# Nguyen_Ly.net
KiCad netlist of a schematic drawn in Altium Designer
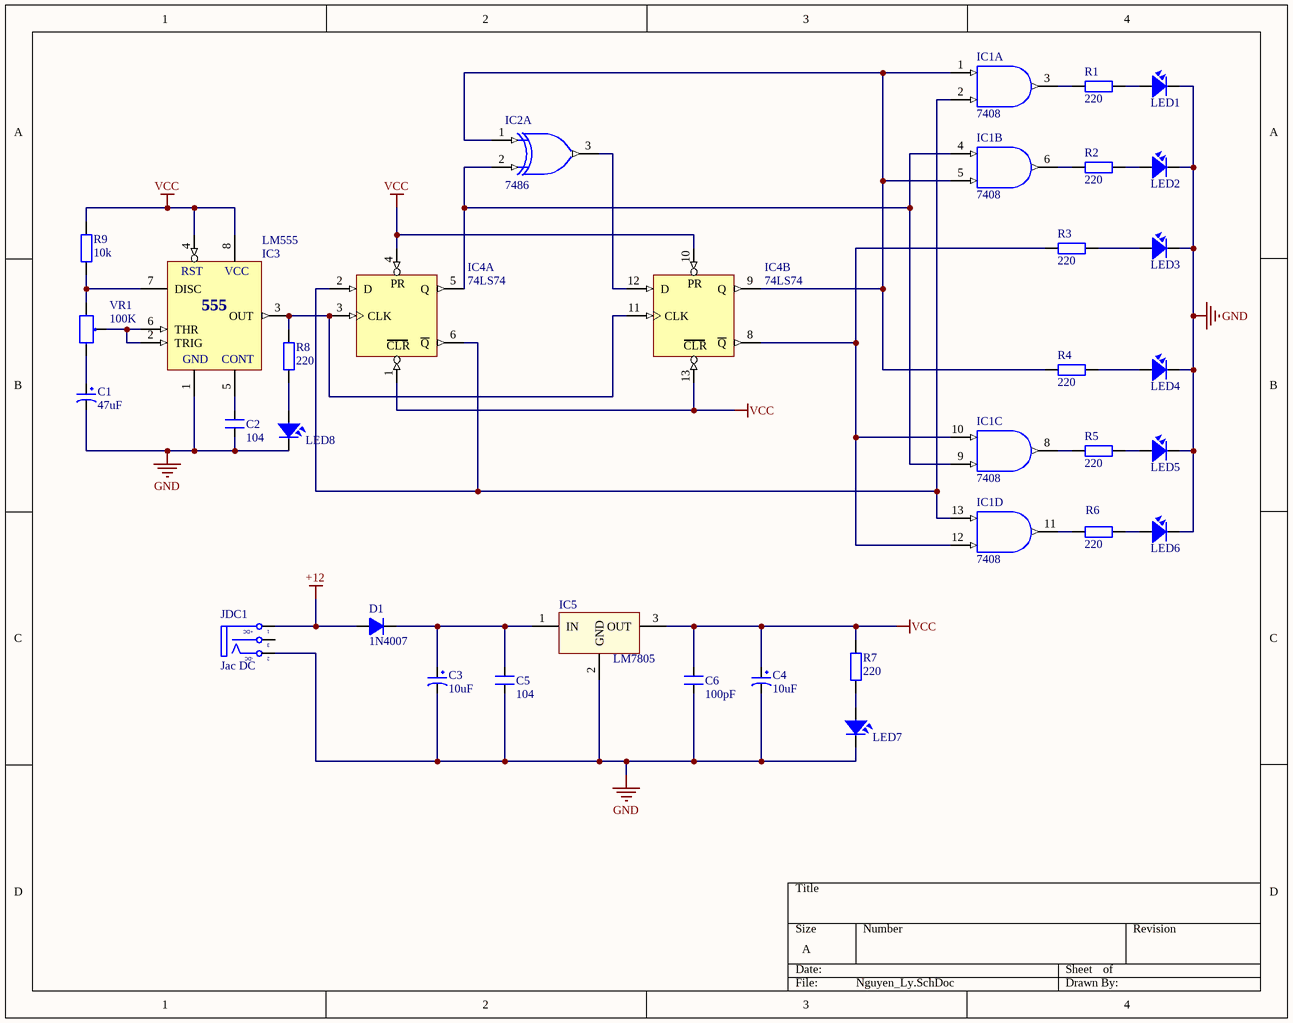
[diagram p0: Nguyen_Ly.SchDoc]

(export (version "E")
  (design (tool "Eeschema 10.0.6"))
  (components
    (comp (ref "C1")
      (value "47uF")
      (footprint "CP1/2")
      (description "Cap P  0,1uF < 22uF , 16 - 50V")
      (libsource (lib "Thuvien3D") (part "CP1"))
    )
    (comp (ref "C2")
      (value "104")
      (footprint "CN1")
      (description "Cap np  1pF - 472pF")
      (libsource (lib "Thuvien3D") (part "CN1"))
    )
    (comp (ref "C3")
      (value "10uF")
      (footprint "CP1/2")
      (description "Cap P  0,1uF < 22uF , 16 - 50V")
      (libsource (lib "Thuvien3D") (part "CP1"))
    )
    (comp (ref "C4")
      (value "10uF")
      (footprint "CP1/2")
      (description "Cap P  0,1uF < 22uF , 16 - 50V")
      (libsource (lib "Thuvien3D") (part "CP1"))
    )
    (comp (ref "C5")
      (value "104")
      (footprint "CN1")
      (description "Cap np  1pF - 472pF")
      (libsource (lib "Thuvien3D") (part "CN1"))
    )
    (comp (ref "C6")
      (value "100pF")
      (footprint "CN1")
      (description "Cap np  1pF - 472pF")
      (libsource (lib "Thuvien3D") (part "CN1"))
    )
    (comp (ref "D1")
      (value "1N4007")
      (footprint "D1A")
      (description "Diode 1A")
      (libsource (lib "Thuvien3D") (part "D1A"))
    )
    (comp (ref "IC1")
      (value "7408")
      (footprint "DIP14/W0.3")
      (description "Quad 2-Input AND Gate")
      (libsource (lib "Thuvien3D") (part "7408"))
    )
    (comp (ref "IC2")
      (value "7486")
      (footprint "DIP14/W0.3")
      (description "Quad 2-Input XOR Gate")
      (fields (field (name "COPYRIGHT BY") "VanDungEvn@Gmail.com"))
      (libsource (lib "Thuvien3D") (part "7486"))
    )
    (comp (ref "IC3")
      (value "LM555")
      (footprint "DIP8/W0.3")
      (description "Timer")
      (libsource (lib "Thuvien3D") (part "LM555"))
    )
    (comp (ref "IC4")
      (value "74LS74")
      (footprint "DIP14/W0.3")
      (description "Dual D Flip-Flop")
      (fields (field (name "COPYRIGHT BY") "VanDungEvn@Gmail.com"))
      (libsource (lib "Thuvien3D") (part "7474"))
    )
    (comp (ref "IC5")
      (value "LM7805")
      (footprint "QTO-220")
      (description "On ap +, from + 5 to + 24VDC")
      (libsource (lib "Thuvien3D") (part "LM78xx"))
    )
    (comp (ref "JDC1")
      (value "Jac DC")
      (footprint "DC-IN")
      (description "Jac DC input")
      (libsource (lib "Thuvien3D") (part "DCIN"))
    )
    (comp (ref "LED1")
      (value "LED")
      (footprint "LED-5-Green")
      (description "LED Single colour Green and Red")
      (libsource (lib "Thuvien3D") (part "LED"))
    )
    (comp (ref "LED2")
      (value "LED")
      (footprint "LED-5-Yellow")
      (description "LED Single colour Green and Red")
      (libsource (lib "Thuvien3D") (part "LED"))
    )
    (comp (ref "LED3")
      (value "LED")
      (footprint "LED-5-RED")
      (description "LED Single colour Green and Red")
      (libsource (lib "Thuvien3D") (part "LED"))
    )
    (comp (ref "LED4")
      (value "LED")
      (footprint "LED-5-RED")
      (description "LED Single colour Green and Red")
      (libsource (lib "Thuvien3D") (part "LED"))
    )
    (comp (ref "LED5")
      (value "LED")
      (footprint "LED-5-Yellow")
      (description "LED Single colour Green and Red")
      (libsource (lib "Thuvien3D") (part "LED"))
    )
    (comp (ref "LED6")
      (value "LED")
      (footprint "LED-5-Green")
      (description "LED Single colour Green and Red")
      (libsource (lib "Thuvien3D") (part "LED"))
    )
    (comp (ref "LED7")
      (value "LED")
      (footprint "LED-5-WHITE")
      (description "LED Single colour Green and Red")
      (libsource (lib "Thuvien3D") (part "LED"))
    )
    (comp (ref "LED8")
      (value "LED")
      (footprint "LED-5-WHITE")
      (description "LED Single colour Green and Red")
      (libsource (lib "Thuvien3D") (part "LED"))
    )
    (comp (ref "R1")
      (value "220")
      (footprint "R1/4W")
      (description "Resistor 1/4W")
      (libsource (lib "Thuvien3D") (part "R1/4W"))
    )
    (comp (ref "R2")
      (value "220")
      (footprint "R1/4W")
      (description "Resistor 1/4W")
      (libsource (lib "Thuvien3D") (part "R1/4W"))
    )
    (comp (ref "R3")
      (value "220")
      (footprint "R1/4W")
      (description "Resistor 1/4W")
      (libsource (lib "Thuvien3D") (part "R1/4W"))
    )
    (comp (ref "R4")
      (value "220")
      (footprint "R1/4W")
      (description "Resistor 1/4W")
      (libsource (lib "Thuvien3D") (part "R1/4W"))
    )
    (comp (ref "R5")
      (value "220")
      (footprint "R1/4W")
      (description "Resistor 1/4W")
      (libsource (lib "Thuvien3D") (part "R1/4W"))
    )
    (comp (ref "R6")
      (value "220")
      (footprint "R1/4W")
      (description "Resistor 1/4W")
      (libsource (lib "Thuvien3D") (part "R1/4W"))
    )
    (comp (ref "R7")
      (value "220")
      (footprint "R1/4W")
      (description "Resistor 1/4W")
      (libsource (lib "Thuvien3D") (part "R1/4W"))
    )
    (comp (ref "R8")
      (value "220")
      (footprint "R1/4W")
      (description "Resistor 1/4W")
      (libsource (lib "Thuvien3D") (part "R1/4W"))
    )
    (comp (ref "R9")
      (value "10k")
      (footprint "R1/4W")
      (description "Resistor 1/4W")
      (libsource (lib "Thuvien3D") (part "R1/4W"))
    )
    (comp (ref "VR1")
      (value "100K")
      (footprint "VR")
      (description "Var Resistor")
      (libsource (lib "Thuvien3D") (part "VR"))
    )
  )
  (nets
    (net (code "1") (name "+12") (class "Default")
      (node (ref "D1") (pin "1") (pinfunction "A_1") (pintype "passive"))
      (node (ref "JDC1") (pin "1") (pinfunction "T_1") (pintype "passive"))
    )
    (net (code "2") (name "GND") (class "Default")
      (node (ref "C1") (pin "2") (pinfunction "2_2") (pintype "passive"))
      (node (ref "C2") (pin "1") (pinfunction "1_1") (pintype "passive"))
      (node (ref "C3") (pin "2") (pinfunction "2_2") (pintype "passive"))
      (node (ref "C4") (pin "2") (pinfunction "2_2") (pintype "passive"))
      (node (ref "C5") (pin "1") (pinfunction "1_1") (pintype "passive"))
      (node (ref "C6") (pin "1") (pinfunction "1_1") (pintype "passive"))
      (node (ref "IC1") (pin "7") (pinfunction "GND_7") (pintype "power_in"))
      (node (ref "IC2") (pin "7") (pinfunction "GND_7") (pintype "power_in"))
      (node (ref "IC3") (pin "1") (pinfunction "GND_1") (pintype "power_in"))
      (node (ref "IC4") (pin "7") (pinfunction "GND_7") (pintype "power_in"))
      (node (ref "IC5") (pin "2") (pinfunction "GND_2") (pintype "passive"))
      (node (ref "JDC1") (pin "2") (pinfunction "TN_2") (pintype "passive"))
      (node (ref "LED1") (pin "2") (pinfunction "2_2") (pintype "passive"))
      (node (ref "LED2") (pin "2") (pinfunction "2_2") (pintype "passive"))
      (node (ref "LED3") (pin "2") (pinfunction "2_2") (pintype "passive"))
      (node (ref "LED4") (pin "2") (pinfunction "2_2") (pintype "passive"))
      (node (ref "LED5") (pin "2") (pinfunction "2_2") (pintype "passive"))
      (node (ref "LED6") (pin "2") (pinfunction "2_2") (pintype "passive"))
      (node (ref "LED7") (pin "2") (pinfunction "2_2") (pintype "passive"))
      (node (ref "LED8") (pin "2") (pinfunction "2_2") (pintype "passive"))
    )
    (net (code "3") (name "Net-(C1-Pad1)") (class "Default")
      (node (ref "C1") (pin "1") (pinfunction "1_1") (pintype "passive"))
      (node (ref "VR1") (pin "3") (pinfunction "3_3") (pintype "passive"))
    )
    (net (code "4") (name "Net-(D1-K)") (class "Default")
      (node (ref "C3") (pin "1") (pinfunction "1_1") (pintype "passive"))
      (node (ref "C5") (pin "2") (pinfunction "2_2") (pintype "passive"))
      (node (ref "D1") (pin "2") (pinfunction "K_2") (pintype "passive"))
      (node (ref "IC5") (pin "1") (pinfunction "IN_1") (pintype "passive"))
    )
    (net (code "5") (name "Net-(IC1A-A)") (class "Default")
      (node (ref "IC1") (pin "1") (pinfunction "A_1") (pintype "input"))
      (node (ref "IC1") (pin "5") (pinfunction "B_5") (pintype "input"))
      (node (ref "IC2") (pin "1") (pinfunction "A_1") (pintype "input"))
      (node (ref "IC4") (pin "9") (pinfunction "Q_9") (pintype "output"))
      (node (ref "R4") (pin "2") (pinfunction "2_2") (pintype "passive"))
    )
    (net (code "6") (name "Net-(IC1A-B)") (class "Default")
      (node (ref "IC1") (pin "13") (pinfunction "A_13") (pintype "input"))
      (node (ref "IC1") (pin "2") (pinfunction "B_2") (pintype "input"))
      (node (ref "IC4") (pin "2") (pinfunction "D_2") (pintype "input"))
      (node (ref "IC4") (pin "6") (pinfunction "~{Q}_6") (pintype "output"))
    )
    (net (code "7") (name "Net-(IC1A-O)") (class "Default")
      (node (ref "IC1") (pin "3") (pinfunction "O_3") (pintype "output"))
      (node (ref "R1") (pin "2") (pinfunction "2_2") (pintype "passive"))
    )
    (net (code "8") (name "Net-(IC1B-A)") (class "Default")
      (node (ref "IC1") (pin "4") (pinfunction "A_4") (pintype "input"))
      (node (ref "IC1") (pin "9") (pinfunction "B_9") (pintype "input"))
      (node (ref "IC2") (pin "2") (pinfunction "B_2") (pintype "input"))
      (node (ref "IC4") (pin "5") (pinfunction "Q_5") (pintype "output"))
    )
    (net (code "9") (name "Net-(IC1B-O)") (class "Default")
      (node (ref "IC1") (pin "6") (pinfunction "O_6") (pintype "output"))
      (node (ref "R2") (pin "2") (pinfunction "2_2") (pintype "passive"))
    )
    (net (code "10") (name "Net-(IC1C-A)") (class "Default")
      (node (ref "IC1") (pin "10") (pinfunction "A_10") (pintype "input"))
      (node (ref "IC1") (pin "12") (pinfunction "B_12") (pintype "input"))
      (node (ref "IC4") (pin "8") (pinfunction "~{Q}_8") (pintype "output"))
      (node (ref "R3") (pin "2") (pinfunction "2_2") (pintype "passive"))
    )
    (net (code "11") (name "Net-(IC1C-O)") (class "Default")
      (node (ref "IC1") (pin "8") (pinfunction "O_8") (pintype "output"))
      (node (ref "R5") (pin "2") (pinfunction "2_2") (pintype "passive"))
    )
    (net (code "12") (name "Net-(IC1D-O)") (class "Default")
      (node (ref "IC1") (pin "11") (pinfunction "O_11") (pintype "output"))
      (node (ref "R6") (pin "2") (pinfunction "2_2") (pintype "passive"))
    )
    (net (code "13") (name "Net-(IC2A-Y)") (class "Default")
      (node (ref "IC2") (pin "3") (pinfunction "Y_3") (pintype "output"))
      (node (ref "IC4") (pin "12") (pinfunction "D_12") (pintype "input"))
    )
    (net (code "14") (name "Net-(IC3-CONT)") (class "Default")
      (node (ref "C2") (pin "2") (pinfunction "2_2") (pintype "passive"))
      (node (ref "IC3") (pin "5") (pinfunction "CONT_5") (pintype "passive"))
    )
    (net (code "15") (name "Net-(IC3-DISC)") (class "Default")
      (node (ref "IC3") (pin "7") (pinfunction "DISC_7") (pintype "open_collector"))
      (node (ref "R9") (pin "1") (pinfunction "1_1") (pintype "passive"))
      (node (ref "VR1") (pin "1") (pinfunction "1_1") (pintype "passive"))
    )
    (net (code "16") (name "Net-(IC3-OUT)") (class "Default")
      (node (ref "IC3") (pin "3") (pinfunction "OUT_3") (pintype "output"))
      (node (ref "IC4") (pin "11") (pinfunction "CLK_11") (pintype "input"))
      (node (ref "IC4") (pin "3") (pinfunction "CLK_3") (pintype "input"))
      (node (ref "R8") (pin "2") (pinfunction "2_2") (pintype "passive"))
    )
    (net (code "17") (name "Net-(IC3-THR)") (class "Default")
      (node (ref "IC3") (pin "2") (pinfunction "TRIG_2") (pintype "input"))
      (node (ref "IC3") (pin "6") (pinfunction "THR_6") (pintype "input"))
      (node (ref "VR1") (pin "2") (pinfunction "2_2") (pintype "passive"))
    )
    (net (code "18") (name "Net-(LED1-Pad1)") (class "Default")
      (node (ref "LED1") (pin "1") (pinfunction "1_1") (pintype "passive"))
      (node (ref "R1") (pin "1") (pinfunction "1_1") (pintype "passive"))
    )
    (net (code "19") (name "Net-(LED2-Pad1)") (class "Default")
      (node (ref "LED2") (pin "1") (pinfunction "1_1") (pintype "passive"))
      (node (ref "R2") (pin "1") (pinfunction "1_1") (pintype "passive"))
    )
    (net (code "20") (name "Net-(LED3-Pad1)") (class "Default")
      (node (ref "LED3") (pin "1") (pinfunction "1_1") (pintype "passive"))
      (node (ref "R3") (pin "1") (pinfunction "1_1") (pintype "passive"))
    )
    (net (code "21") (name "Net-(LED4-Pad1)") (class "Default")
      (node (ref "LED4") (pin "1") (pinfunction "1_1") (pintype "passive"))
      (node (ref "R4") (pin "1") (pinfunction "1_1") (pintype "passive"))
    )
    (net (code "22") (name "Net-(LED5-Pad1)") (class "Default")
      (node (ref "LED5") (pin "1") (pinfunction "1_1") (pintype "passive"))
      (node (ref "R5") (pin "1") (pinfunction "1_1") (pintype "passive"))
    )
    (net (code "23") (name "Net-(LED6-Pad1)") (class "Default")
      (node (ref "LED6") (pin "1") (pinfunction "1_1") (pintype "passive"))
      (node (ref "R6") (pin "1") (pinfunction "1_1") (pintype "passive"))
    )
    (net (code "24") (name "Net-(LED7-Pad1)") (class "Default")
      (node (ref "LED7") (pin "1") (pinfunction "1_1") (pintype "passive"))
      (node (ref "R7") (pin "2") (pinfunction "2_2") (pintype "passive"))
    )
    (net (code "25") (name "Net-(LED8-Pad1)") (class "Default")
      (node (ref "LED8") (pin "1") (pinfunction "1_1") (pintype "passive"))
      (node (ref "R8") (pin "1") (pinfunction "1_1") (pintype "passive"))
    )
    (net (code "26") (name "VCC") (class "Default")
      (node (ref "C4") (pin "1") (pinfunction "1_1") (pintype "passive"))
      (node (ref "C6") (pin "2") (pinfunction "2_2") (pintype "passive"))
      (node (ref "IC1") (pin "14") (pinfunction "VCC_14") (pintype "power_in"))
      (node (ref "IC3") (pin "4") (pinfunction "RST_4") (pintype "input"))
      (node (ref "IC3") (pin "8") (pinfunction "VCC_8") (pintype "power_in"))
      (node (ref "IC4") (pin "1") (pinfunction "CLR_1") (pintype "input"))
      (node (ref "IC4") (pin "10") (pinfunction "PR_10") (pintype "input"))
      (node (ref "IC4") (pin "13") (pinfunction "CLR_13") (pintype "input"))
      (node (ref "IC4") (pin "14") (pinfunction "VCC_14") (pintype "power_in"))
      (node (ref "IC4") (pin "4") (pinfunction "PR_4") (pintype "input"))
      (node (ref "IC5") (pin "3") (pinfunction "OUT_3") (pintype "passive"))
      (node (ref "R7") (pin "1") (pinfunction "1_1") (pintype "passive"))
      (node (ref "R9") (pin "2") (pinfunction "2_2") (pintype "passive"))
    )
    (net (code "27") (name "VDD") (class "Default")
      (node (ref "IC2") (pin "14") (pinfunction "VDD_14") (pintype "power_in"))
    )
    (net (code "28") (name "unconnected-(JDC1-S-Pad3)") (class "Default")
      (node (ref "JDC1") (pin "3") (pinfunction "S_3") (pintype "power_in"))
    )
  )
)
